# TimesDetector.net
KiCad netlist of a schematic drawn in EAGLE
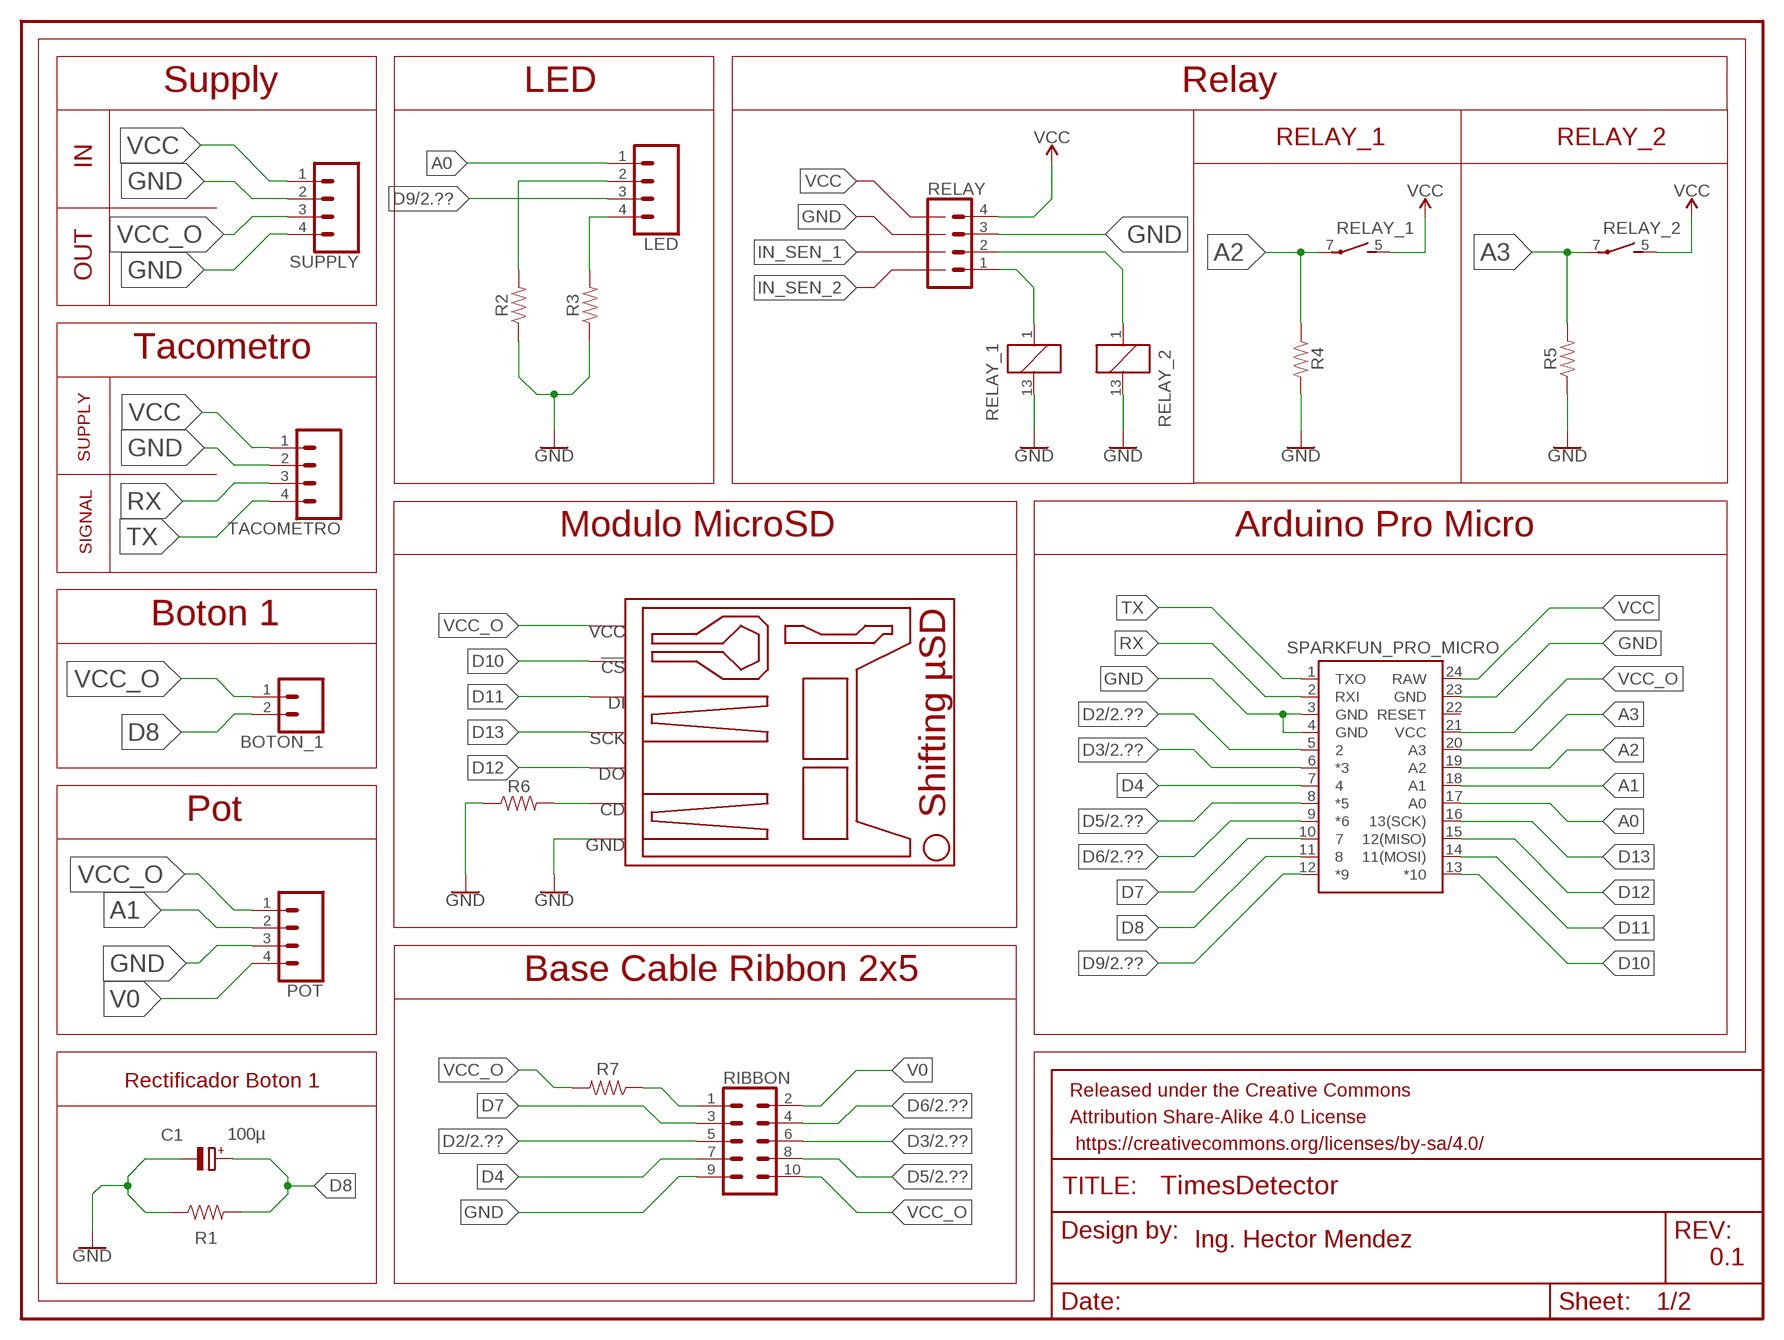
[diagram p0: schematic, sheet 1]
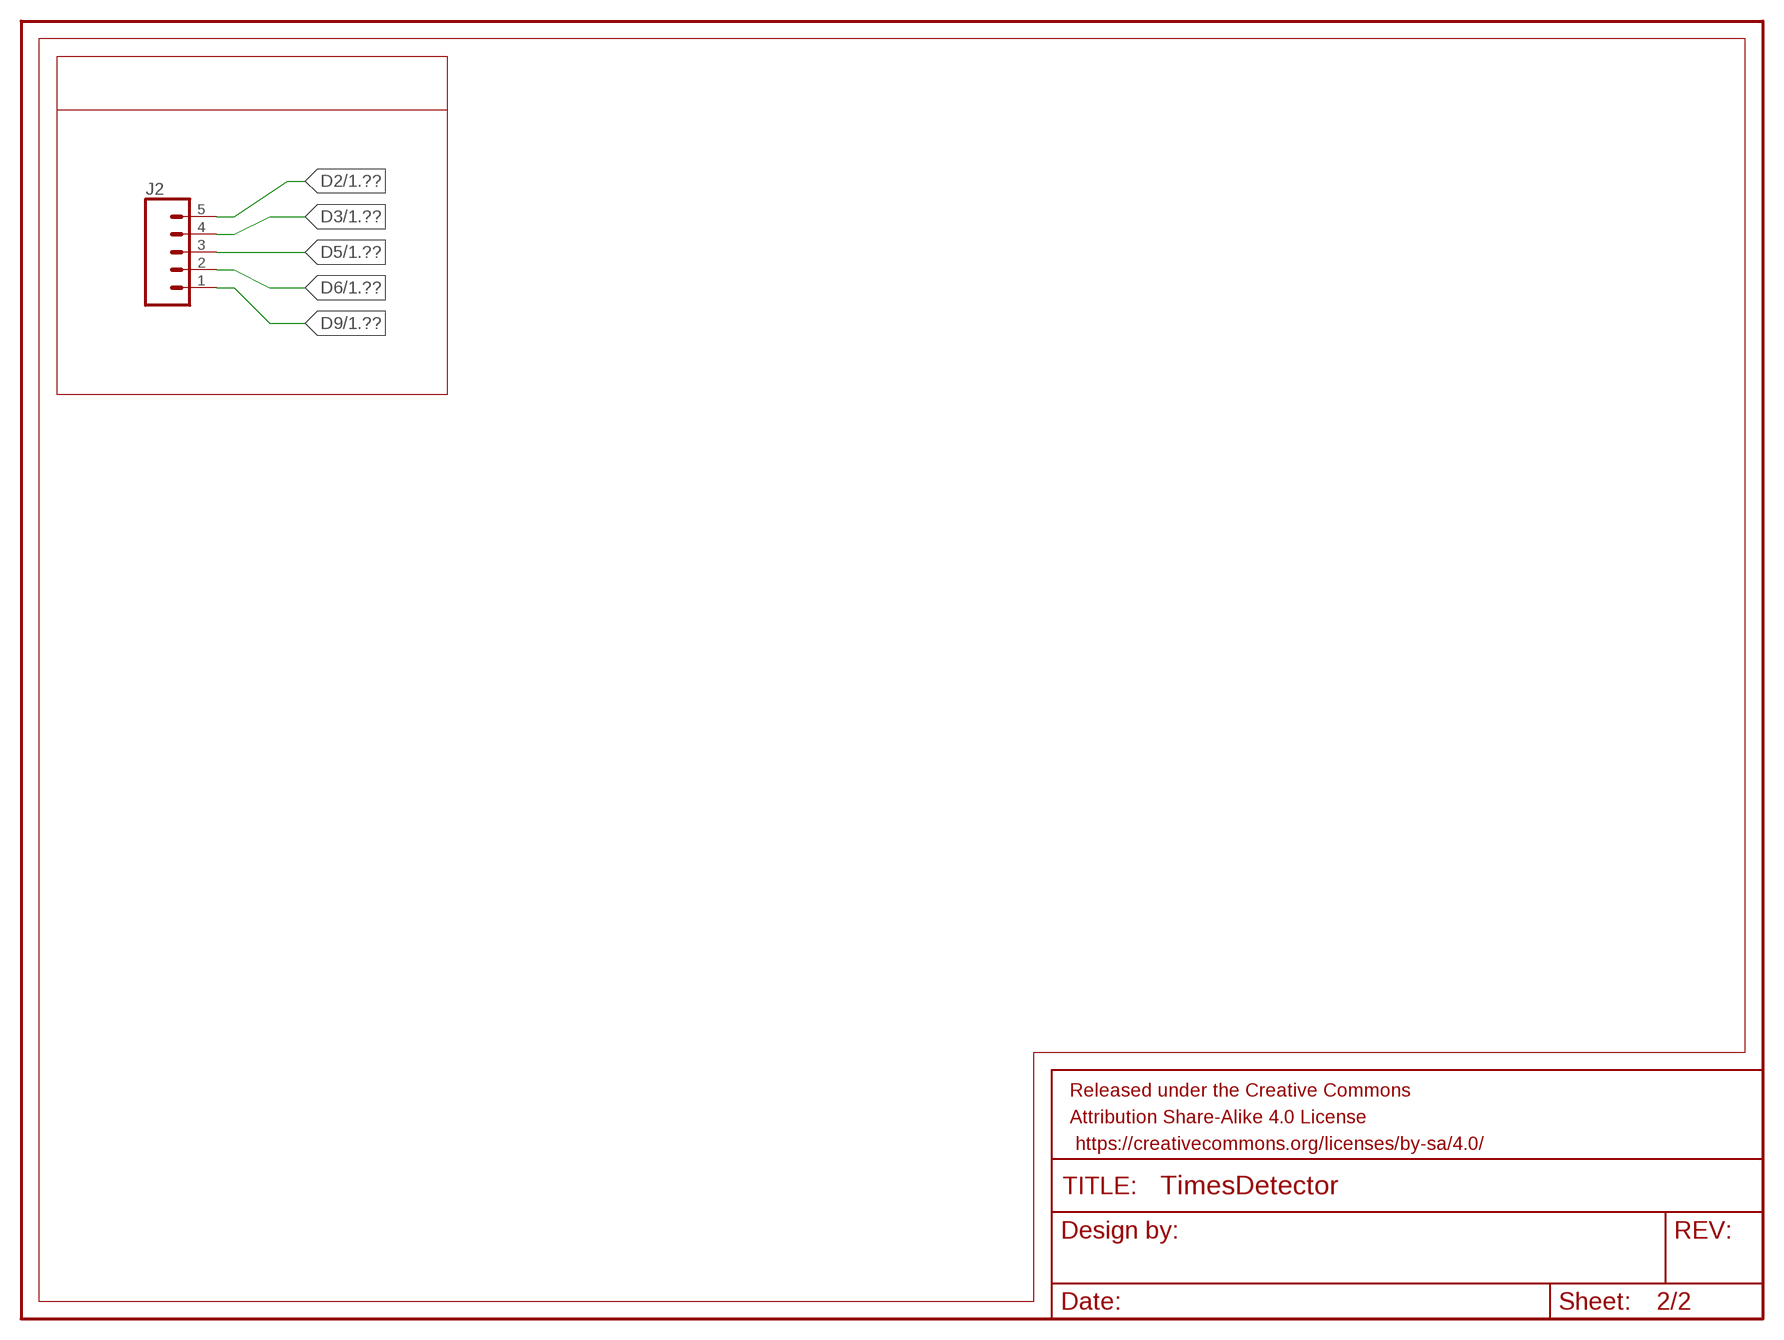
[diagram p1: schematic, sheet 2]

(export (version "E")
  (design (tool "Eeschema 10.0.6"))
  (components
    (comp (ref "FRAME3")
      (value "FRAME-LETTERNO_PACKAGE")
      (footprint "eagle-import:DUMMY")
      (fields (field (name "DESIGNER") "Nobody"))
      (libsource (lib "eagle-import") (part "FRAME-LETTERNO_PACKAGE"))
    )
    (comp (ref "J2")
      (value "CONN_05PTH_LONGPADS")
      (footprint "eagle-import:1X05_LONGPADS")
      (libsource (lib "eagle-import") (part "CONN_05PTH_LONGPADS"))
    )
    (comp (ref "B1")
      (value "SPARKFUN_PRO_MICRO")
      (footprint "eagle-import:SPARKFUN_PRO_MICRO")
      (libsource (lib "eagle-import") (part "SPARKFUN_PRO_MICRO"))
    )
    (comp (ref "BOTON_1")
      (value "CONN_025MM")
      (footprint "eagle-import:SCREWTERMINAL-5MM-2")
      (libsource (lib "eagle-import") (part "CONN_025MM"))
    )
    (comp (ref "C1")
      (value "100µ")
      (footprint "eagle-import:E2,5-6E")
      (libsource (lib "eagle-import") (part "CPOL-EUE2,5-6E"))
    )
    (comp (ref "FRAME1")
      (value "FRAME-LETTER")
      (footprint "eagle-import:CREATIVE_COMMONS")
      (libsource (lib "eagle-import") (part "FRAME-LETTER"))
    )
    (comp (ref "LED")
      (value "CONN_04SCREW_LOCK")
      (footprint "eagle-import:SCREWTERMINAL-3.5MM-4_LOCK")
      (libsource (lib "eagle-import") (part "CONN_04SCREW_LOCK"))
    )
    (comp (ref "MODULE1")
      (value "MICROSD_SPARKFUN_LEVEL_SHIFTING_MODULE")
      (footprint "eagle-import:MICROSD_SPARKFUN_LEVEL_SHFTING_MODULE")
      (libsource (lib "eagle-import") (part "MICROSD_SPARKFUN_LEVEL_SHIFTING_MODULE"))
    )
    (comp (ref "POT")
      (value "CONN_04SCREW_LOCK")
      (footprint "eagle-import:SCREWTERMINAL-3.5MM-4_LOCK")
      (libsource (lib "eagle-import") (part "CONN_04SCREW_LOCK"))
    )
    (comp (ref "R1")
      (value "RESISTORAXIAL-0.3")
      (footprint "eagle-import:AXIAL-0.3")
      (libsource (lib "eagle-import") (part "RESISTORAXIAL-0.3"))
    )
    (comp (ref "R2")
      (value "RESISTORAXIAL-0.3")
      (footprint "eagle-import:AXIAL-0.3")
      (libsource (lib "eagle-import") (part "RESISTORAXIAL-0.3"))
    )
    (comp (ref "R3")
      (value "RESISTORAXIAL-0.3")
      (footprint "eagle-import:AXIAL-0.3")
      (libsource (lib "eagle-import") (part "RESISTORAXIAL-0.3"))
    )
    (comp (ref "R4")
      (value "RESISTORAXIAL-0.3")
      (footprint "eagle-import:AXIAL-0.3")
      (libsource (lib "eagle-import") (part "RESISTORAXIAL-0.3"))
    )
    (comp (ref "R5")
      (value "RESISTORAXIAL-0.3")
      (footprint "eagle-import:AXIAL-0.3")
      (libsource (lib "eagle-import") (part "RESISTORAXIAL-0.3"))
    )
    (comp (ref "R6")
      (value "RESISTORAXIAL-0.3")
      (footprint "eagle-import:AXIAL-0.3")
      (libsource (lib "eagle-import") (part "RESISTORAXIAL-0.3"))
    )
    (comp (ref "R7")
      (value "RESISTORAXIAL-0.3")
      (footprint "eagle-import:AXIAL-0.3")
      (libsource (lib "eagle-import") (part "RESISTORAXIAL-0.3"))
    )
    (comp (ref "RELAY")
      (value "CONN_04SCREW_LOCK")
      (footprint "eagle-import:SCREWTERMINAL-3.5MM-4_LOCK")
      (libsource (lib "eagle-import") (part "CONN_04SCREW_LOCK"))
    )
    (comp (ref "RELAY_1")
      (value "G6D-1A-ASI12VDC")
      (footprint "eagle-import:G6D")
      (libsource (lib "eagle-import") (part "G6D?-1A-ASI12VDC"))
    )
    (comp (ref "RELAY_2")
      (value "G6D-1A-ASI12VDC")
      (footprint "eagle-import:G6D")
      (libsource (lib "eagle-import") (part "G6D?-1A-ASI12VDC"))
    )
    (comp (ref "RIBBON")
      (value "CONN_05X2SHD")
      (footprint "eagle-import:2X5-SHROUDED")
      (libsource (lib "eagle-import") (part "CONN_05X2SHD"))
    )
    (comp (ref "SUPPLY")
      (value "CONN_04SCREW_LOCK")
      (footprint "eagle-import:SCREWTERMINAL-3.5MM-4_LOCK")
      (libsource (lib "eagle-import") (part "CONN_04SCREW_LOCK"))
    )
    (comp (ref "TACOMETRO")
      (value "CONN_04SCREW_LOCK")
      (footprint "eagle-import:SCREWTERMINAL-3.5MM-4_LOCK")
      (libsource (lib "eagle-import") (part "CONN_04SCREW_LOCK"))
    )
  )
  (nets
    (net (code "1") (name "A0") (class "Default")
      (node (ref "B1") (pin "17") (pinfunction "A0_17") (pintype "bidirectional"))
      (node (ref "LED") (pin "1") (pinfunction "1_1") (pintype "passive"))
    )
    (net (code "2") (name "A1") (class "Default")
      (node (ref "B1") (pin "18") (pinfunction "A1_18") (pintype "bidirectional"))
      (node (ref "POT") (pin "2") (pinfunction "2_2") (pintype "passive"))
    )
    (net (code "3") (name "A2") (class "Default")
      (node (ref "B1") (pin "19") (pinfunction "A2_19") (pintype "bidirectional"))
      (node (ref "R4") (pin "P$1") (pinfunction "1_P$1") (pintype "passive"))
      (node (ref "RELAY_1") (pin "7") (pinfunction "P_7") (pintype "passive"))
    )
    (net (code "4") (name "A3") (class "Default")
      (node (ref "B1") (pin "20") (pinfunction "A3_20") (pintype "bidirectional"))
      (node (ref "R5") (pin "P$2") (pinfunction "2_P$2") (pintype "passive"))
      (node (ref "RELAY_2") (pin "7") (pinfunction "P_7") (pintype "passive"))
    )
    (net (code "5") (name "D2") (class "Default")
      (node (ref "B1") (pin "5") (pinfunction "2_5") (pintype "bidirectional"))
      (node (ref "J2") (pin "5") (pinfunction "5_5") (pintype "passive"))
      (node (ref "RIBBON") (pin "5") (pinfunction "5_5") (pintype "passive"))
    )
    (net (code "6") (name "D3") (class "Default")
      (node (ref "B1") (pin "6") (pinfunction "*3_6") (pintype "bidirectional"))
      (node (ref "J2") (pin "4") (pinfunction "4_4") (pintype "passive"))
      (node (ref "RIBBON") (pin "6") (pinfunction "6_6") (pintype "passive"))
    )
    (net (code "7") (name "D4") (class "Default")
      (node (ref "B1") (pin "7") (pinfunction "4_7") (pintype "bidirectional"))
      (node (ref "RIBBON") (pin "7") (pinfunction "7_7") (pintype "passive"))
    )
    (net (code "8") (name "D5") (class "Default")
      (node (ref "B1") (pin "8") (pinfunction "*5_8") (pintype "bidirectional"))
      (node (ref "J2") (pin "3") (pinfunction "3_3") (pintype "passive"))
      (node (ref "RIBBON") (pin "8") (pinfunction "8_8") (pintype "passive"))
    )
    (net (code "9") (name "D6") (class "Default")
      (node (ref "B1") (pin "9") (pinfunction "*6_9") (pintype "bidirectional"))
      (node (ref "J2") (pin "2") (pinfunction "2_2") (pintype "passive"))
      (node (ref "RIBBON") (pin "4") (pinfunction "4_4") (pintype "passive"))
    )
    (net (code "10") (name "D7") (class "Default")
      (node (ref "B1") (pin "10") (pinfunction "7_10") (pintype "bidirectional"))
      (node (ref "RIBBON") (pin "3") (pinfunction "3_3") (pintype "passive"))
    )
    (net (code "11") (name "D8") (class "Default")
      (node (ref "B1") (pin "11") (pinfunction "8_11") (pintype "bidirectional"))
      (node (ref "BOTON_1") (pin "2") (pinfunction "2_2") (pintype "passive"))
      (node (ref "C1") (pin "+") (pinfunction "+_+") (pintype "passive"))
      (node (ref "R1") (pin "P$2") (pinfunction "2_P$2") (pintype "passive"))
    )
    (net (code "12") (name "D9") (class "Default")
      (node (ref "B1") (pin "12") (pinfunction "*9_12") (pintype "bidirectional"))
      (node (ref "J2") (pin "1") (pinfunction "1_1") (pintype "passive"))
      (node (ref "LED") (pin "3") (pinfunction "3_3") (pintype "passive"))
    )
    (net (code "13") (name "D10") (class "Default")
      (node (ref "B1") (pin "13") (pinfunction "*10_13") (pintype "bidirectional"))
      (node (ref "MODULE1") (pin "P_!CS") (pinfunction "P_~{CS}_P_!CS") (pintype "bidirectional"))
    )
    (net (code "14") (name "D11") (class "Default")
      (node (ref "B1") (pin "14") (pinfunction "11(MOSI)_14") (pintype "bidirectional"))
      (node (ref "MODULE1") (pin "P_DI") (pinfunction "P_DI_P_DI") (pintype "bidirectional"))
    )
    (net (code "15") (name "D12") (class "Default")
      (node (ref "B1") (pin "15") (pinfunction "12(MISO)_15") (pintype "bidirectional"))
      (node (ref "MODULE1") (pin "P_DO") (pinfunction "P_DO_P_DO") (pintype "bidirectional"))
    )
    (net (code "16") (name "D13") (class "Default")
      (node (ref "B1") (pin "16") (pinfunction "13(SCK)_16") (pintype "bidirectional"))
      (node (ref "MODULE1") (pin "P_SCK") (pinfunction "P_SCK_P_SCK") (pintype "bidirectional"))
    )
    (net (code "17") (name "GND") (class "Default")
      (node (ref "B1") (pin "23") (pinfunction "GND_23") (pintype "power_in"))
      (node (ref "B1") (pin "3") (pinfunction "GND_3") (pintype "power_in"))
      (node (ref "B1") (pin "4") (pinfunction "GND_4") (pintype "power_in"))
      (node (ref "C1") (pin "-") (pinfunction "-_-") (pintype "passive"))
      (node (ref "MODULE1") (pin "P_GND") (pinfunction "GND_P_GND") (pintype "bidirectional"))
      (node (ref "POT") (pin "3") (pinfunction "3_3") (pintype "passive"))
      (node (ref "R1") (pin "P$1") (pinfunction "1_P$1") (pintype "passive"))
      (node (ref "R2") (pin "P$1") (pinfunction "1_P$1") (pintype "passive"))
      (node (ref "R3") (pin "P$1") (pinfunction "1_P$1") (pintype "passive"))
      (node (ref "R4") (pin "P$2") (pinfunction "2_P$2") (pintype "passive"))
      (node (ref "R5") (pin "P$1") (pinfunction "1_P$1") (pintype "passive"))
      (node (ref "R6") (pin "P$1") (pinfunction "1_P$1") (pintype "passive"))
      (node (ref "RELAY") (pin "3") (pinfunction "3_3") (pintype "passive"))
      (node (ref "RELAY_1") (pin "13") (pinfunction "2_13") (pintype "passive"))
      (node (ref "RELAY_2") (pin "13") (pinfunction "2_13") (pintype "passive"))
      (node (ref "RIBBON") (pin "9") (pinfunction "9_9") (pintype "passive"))
      (node (ref "SUPPLY") (pin "2") (pinfunction "2_2") (pintype "passive"))
      (node (ref "SUPPLY") (pin "4") (pinfunction "4_4") (pintype "passive"))
      (node (ref "TACOMETRO") (pin "2") (pinfunction "2_2") (pintype "passive"))
    )
    (net (code "18") (name "IN_SEN_1") (class "Default")
      (node (ref "RELAY") (pin "2") (pinfunction "2_2") (pintype "passive"))
      (node (ref "RELAY_2") (pin "1") (pinfunction "1_1") (pintype "passive"))
    )
    (net (code "19") (name "IN_SEN_2") (class "Default")
      (node (ref "RELAY") (pin "1") (pinfunction "1_1") (pintype "passive"))
      (node (ref "RELAY_1") (pin "1") (pinfunction "1_1") (pintype "passive"))
    )
    (net (code "20") (name "Net-(R2-2)") (class "Default")
      (node (ref "LED") (pin "2") (pinfunction "2_2") (pintype "passive"))
      (node (ref "R2") (pin "P$2") (pinfunction "2_P$2") (pintype "passive"))
    )
    (net (code "21") (name "Net-(R3-2)") (class "Default")
      (node (ref "LED") (pin "4") (pinfunction "4_4") (pintype "passive"))
      (node (ref "R3") (pin "P$2") (pinfunction "2_P$2") (pintype "passive"))
    )
    (net (code "22") (name "Net-(R6-2)") (class "Default")
      (node (ref "MODULE1") (pin "P_CD") (pinfunction "P_CD_P_CD") (pintype "bidirectional"))
      (node (ref "R6") (pin "P$2") (pinfunction "2_P$2") (pintype "passive"))
    )
    (net (code "23") (name "Net-(R7-1)") (class "Default")
      (node (ref "R7") (pin "P$1") (pinfunction "1_P$1") (pintype "passive"))
      (node (ref "RIBBON") (pin "1") (pinfunction "1_1") (pintype "passive"))
    )
    (net (code "24") (name "RX") (class "Default")
      (node (ref "B1") (pin "2") (pinfunction "RXI_2") (pintype "bidirectional"))
      (node (ref "TACOMETRO") (pin "3") (pinfunction "3_3") (pintype "passive"))
    )
    (net (code "25") (name "TX") (class "Default")
      (node (ref "B1") (pin "1") (pinfunction "TXO_1") (pintype "bidirectional"))
      (node (ref "TACOMETRO") (pin "4") (pinfunction "4_4") (pintype "passive"))
    )
    (net (code "26") (name "V0") (class "Default")
      (node (ref "POT") (pin "4") (pinfunction "4_4") (pintype "passive"))
      (node (ref "RIBBON") (pin "2") (pinfunction "2_2") (pintype "passive"))
    )
    (net (code "27") (name "VCC") (class "Default")
      (node (ref "B1") (pin "24") (pinfunction "RAW_24") (pintype "power_in"))
      (node (ref "RELAY") (pin "4") (pinfunction "4_4") (pintype "passive"))
      (node (ref "RELAY_1") (pin "5") (pinfunction "S_5") (pintype "passive"))
      (node (ref "RELAY_2") (pin "5") (pinfunction "S_5") (pintype "passive"))
      (node (ref "SUPPLY") (pin "1") (pinfunction "1_1") (pintype "passive"))
      (node (ref "TACOMETRO") (pin "1") (pinfunction "1_1") (pintype "passive"))
    )
    (net (code "28") (name "VCC_O") (class "Default")
      (node (ref "B1") (pin "21") (pinfunction "VCC_21") (pintype "power_in"))
      (node (ref "BOTON_1") (pin "1") (pinfunction "1_1") (pintype "passive"))
      (node (ref "MODULE1") (pin "P_VCC") (pinfunction "P_VCC_P_VCC") (pintype "bidirectional"))
      (node (ref "POT") (pin "1") (pinfunction "1_1") (pintype "passive"))
      (node (ref "R7") (pin "P$2") (pinfunction "2_P$2") (pintype "passive"))
      (node (ref "RIBBON") (pin "10") (pinfunction "10_10") (pintype "passive"))
      (node (ref "SUPPLY") (pin "3") (pinfunction "3_3") (pintype "passive"))
    )
    (net (code "29") (name "unconnected-(B1-RESET-Pad22)") (class "Default")
      (node (ref "B1") (pin "22") (pinfunction "RESET_22") (pintype "bidirectional"))
    )
  )
)
